# sEHnsor.net
KiCad netlist of a schematic drawn in EAGLE
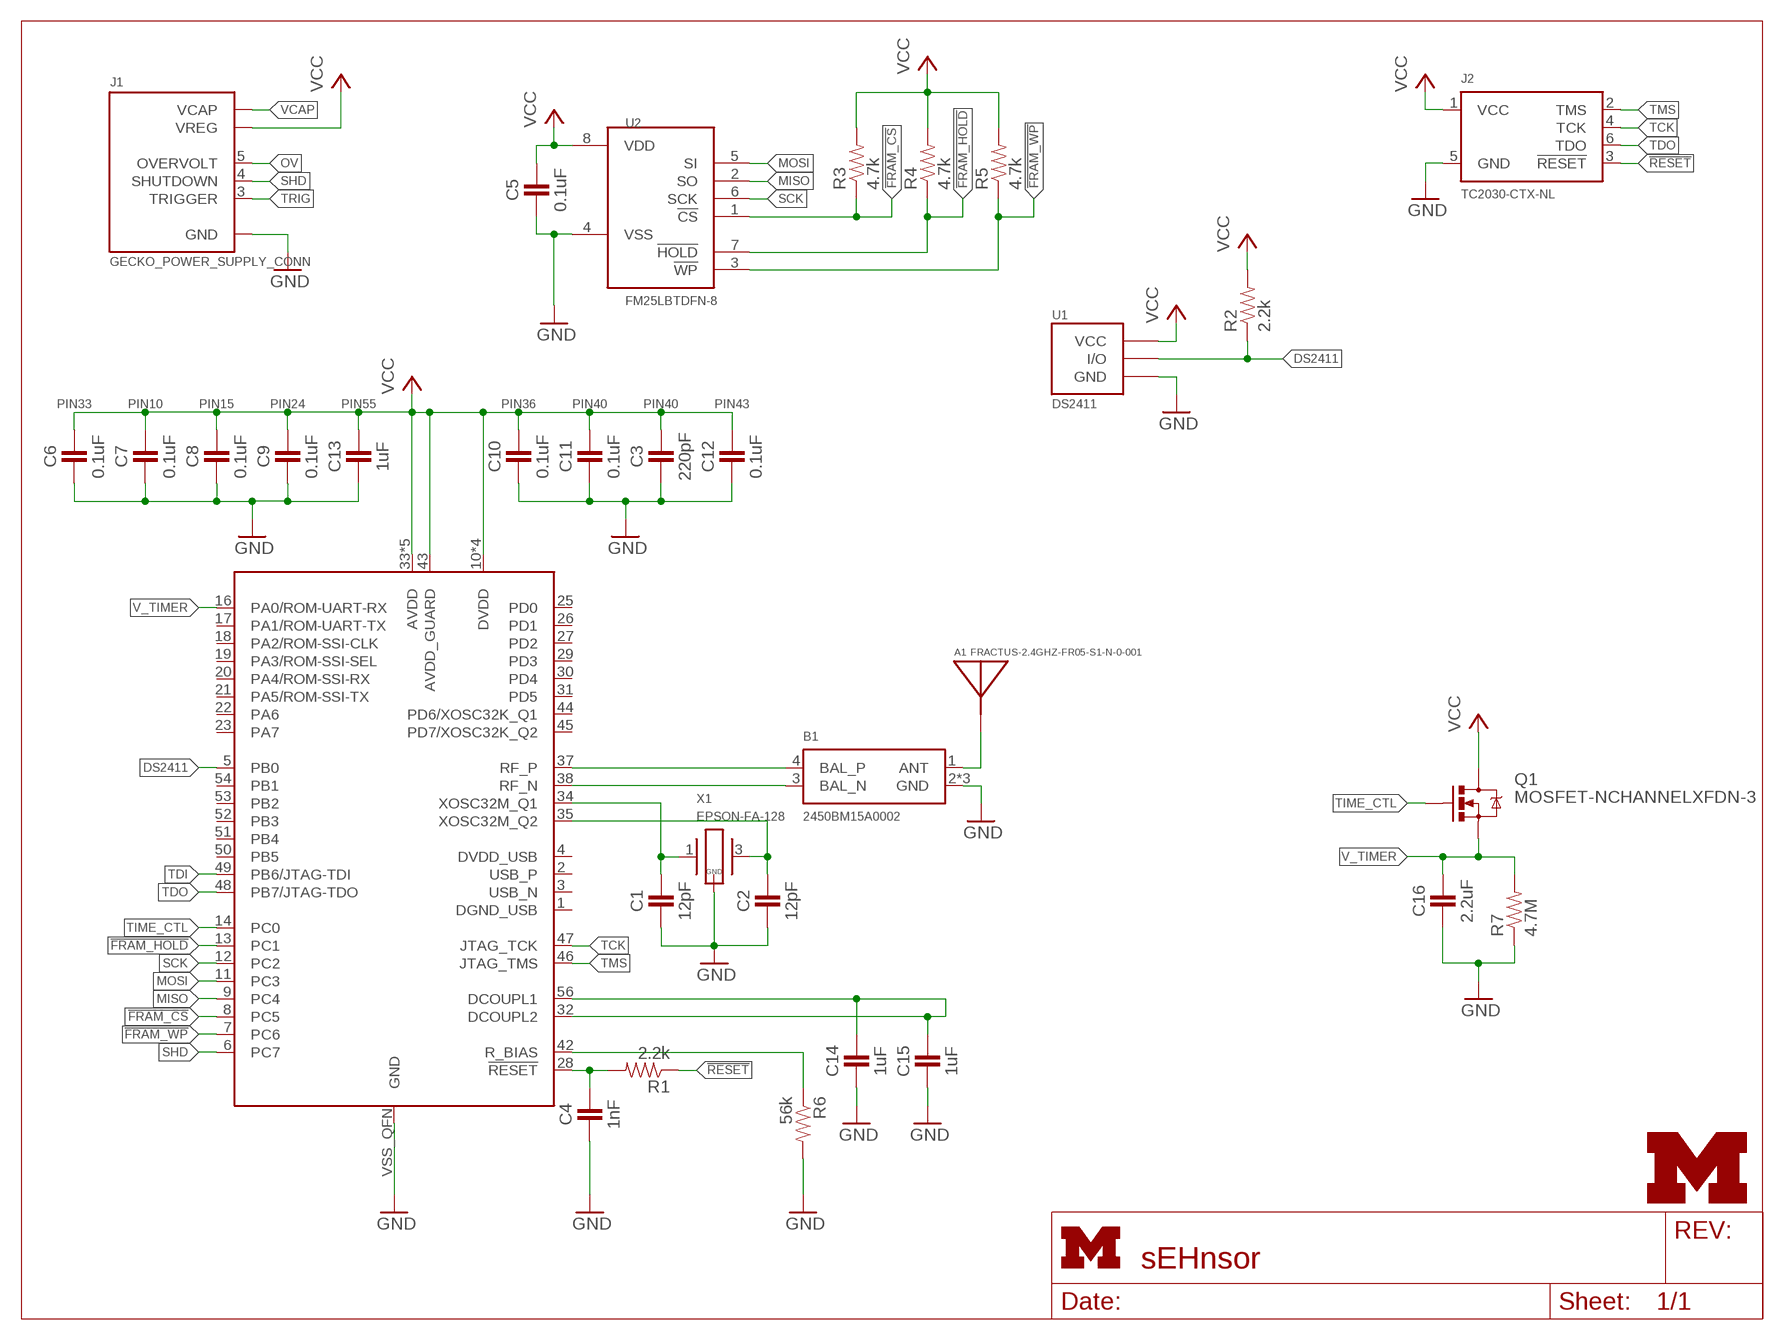
[diagram p0: schematic, sheet 1]

(export (version "E")
  (design (tool "Eeschema 10.0.6"))
  (components
    (comp (ref "A1")
      (value "FRACTUS-2.4GHZ-FR05-S1-N-0-001")
      (footprint "eagle-import:FRACTUS-ANTENNA-FR05-S1-N-0-001")
      (libsource (lib "eagle-import") (part "FRACTUS-2.4GHZ-FR05-S1-N-0-001"))
    )
    (comp (ref "B1")
      (value "2450BM15A0002")
      (footprint "eagle-import:2450BM")
      (libsource (lib "eagle-import") (part "2450BM15A0002"))
    )
    (comp (ref "C1")
      (value "12pF")
      (footprint "eagle-import:0402_CAP")
      (libsource (lib "eagle-import") (part "CAPACITOR"))
    )
    (comp (ref "C2")
      (value "12pF")
      (footprint "eagle-import:0402_CAP")
      (libsource (lib "eagle-import") (part "CAPACITOR"))
    )
    (comp (ref "C3")
      (value "220pF")
      (footprint "eagle-import:0402_CAP")
      (libsource (lib "eagle-import") (part "CAPACITOR"))
    )
    (comp (ref "C4")
      (value "1nF")
      (footprint "eagle-import:0402_CAP")
      (libsource (lib "eagle-import") (part "CAPACITOR"))
    )
    (comp (ref "C5")
      (value "0.1uF")
      (footprint "eagle-import:0402_CAP")
      (libsource (lib "eagle-import") (part "CAPACITOR"))
    )
    (comp (ref "C6")
      (value "0.1uF")
      (footprint "eagle-import:0402_CAP")
      (libsource (lib "eagle-import") (part "CAPACITOR"))
    )
    (comp (ref "C7")
      (value "0.1uF")
      (footprint "eagle-import:0402_CAP")
      (libsource (lib "eagle-import") (part "CAPACITOR"))
    )
    (comp (ref "C8")
      (value "0.1uF")
      (footprint "eagle-import:0402_CAP")
      (libsource (lib "eagle-import") (part "CAPACITOR"))
    )
    (comp (ref "C9")
      (value "0.1uF")
      (footprint "eagle-import:0402_CAP")
      (libsource (lib "eagle-import") (part "CAPACITOR"))
    )
    (comp (ref "C10")
      (value "0.1uF")
      (footprint "eagle-import:0402_CAP")
      (libsource (lib "eagle-import") (part "CAPACITOR"))
    )
    (comp (ref "C11")
      (value "0.1uF")
      (footprint "eagle-import:0402_CAP")
      (libsource (lib "eagle-import") (part "CAPACITOR"))
    )
    (comp (ref "C12")
      (value "0.1uF")
      (footprint "eagle-import:0402_CAP")
      (libsource (lib "eagle-import") (part "CAPACITOR"))
    )
    (comp (ref "C13")
      (value "1uF")
      (footprint "eagle-import:0402_CAP")
      (libsource (lib "eagle-import") (part "CAPACITOR"))
    )
    (comp (ref "C14")
      (value "1uF")
      (footprint "eagle-import:0402_CAP")
      (libsource (lib "eagle-import") (part "CAPACITOR"))
    )
    (comp (ref "C15")
      (value "1uF")
      (footprint "eagle-import:0402_CAP")
      (libsource (lib "eagle-import") (part "CAPACITOR"))
    )
    (comp (ref "C16")
      (value "2.2uF")
      (footprint "eagle-import:0402_CAP")
      (libsource (lib "eagle-import") (part "CAPACITOR"))
    )
    (comp (ref "J1")
      (value "GECKO_POWER_SUPPLY_CONN")
      (footprint "eagle-import:HEADER1X6_0.05IN")
      (libsource (lib "eagle-import") (part "GECKO_POWER_SUPPLY_CONN"))
    )
    (comp (ref "J2")
      (value "TC2030-CTX-NL")
      (footprint "eagle-import:TC2030-IDC-NL")
      (libsource (lib "eagle-import") (part "TC2030-CTX-NL"))
    )
    (comp (ref "Q1")
      (value "MOSFET-NCHANNELXFDN-3")
      (footprint "eagle-import:XFDFN-3")
      (libsource (lib "eagle-import") (part "MOSFET-NCHANNELXFDN-3"))
    )
    (comp (ref "R1")
      (value "2.2k")
      (footprint "eagle-import:0402_RES")
      (libsource (lib "eagle-import") (part "RESISTOR"))
    )
    (comp (ref "R2")
      (value "2.2k")
      (footprint "eagle-import:0402_RES")
      (libsource (lib "eagle-import") (part "RESISTOR"))
    )
    (comp (ref "R3")
      (value "4.7k")
      (footprint "eagle-import:0402_RES")
      (libsource (lib "eagle-import") (part "RESISTOR"))
    )
    (comp (ref "R4")
      (value "4.7k")
      (footprint "eagle-import:0402_RES")
      (libsource (lib "eagle-import") (part "RESISTOR"))
    )
    (comp (ref "R5")
      (value "4.7k")
      (footprint "eagle-import:0402_RES")
      (libsource (lib "eagle-import") (part "RESISTOR"))
    )
    (comp (ref "R6")
      (value "56k")
      (footprint "eagle-import:0402_RES")
      (libsource (lib "eagle-import") (part "RESISTOR"))
    )
    (comp (ref "R7")
      (value "4.7M")
      (footprint "eagle-import:0402_RES")
      (libsource (lib "eagle-import") (part "RESISTOR"))
    )
    (comp (ref "U$1")
      (value "UMICH_SOLID_SMALL")
      (footprint "eagle-import:UMICH_SOLID_75MIL")
      (libsource (lib "eagle-import") (part "UMICH_SOLID_SMALL"))
    )
    (comp (ref "U1")
      (value "DS2411")
      (footprint "eagle-import:SOT-23")
      (libsource (lib "eagle-import") (part "DS2411"))
    )
    (comp (ref "U2")
      (value "FM25LBTDFN-8")
      (footprint "eagle-import:TDFN-8")
      (libsource (lib "eagle-import") (part "FM25LBTDFN-8"))
    )
    (comp (ref "U3")
      (value "CC2538")
      (footprint "eagle-import:S-PVQFN-N56")
      (libsource (lib "eagle-import") (part "CC2538"))
    )
    (comp (ref "X1")
      (value "EPSON-FA-128")
      (footprint "eagle-import:FA-128")
      (libsource (lib "eagle-import") (part "EPSON-FA-128"))
    )
  )
  (nets
    (net (code "1") (name "/~{FRAM_CS}") (class "Default")
      (node (ref "R3") (pin "1") (pinfunction "1_1") (pintype "passive"))
      (node (ref "U2") (pin "1") (pinfunction "~{CS}_1") (pintype "bidirectional"))
      (node (ref "U3") (pin "8") (pinfunction "PC5_8") (pintype "bidirectional"))
    )
    (net (code "2") (name "/~{FRAM_HOLD}") (class "Default")
      (node (ref "R4") (pin "1") (pinfunction "1_1") (pintype "passive"))
      (node (ref "U2") (pin "7") (pinfunction "~{HOLD}_7") (pintype "bidirectional"))
      (node (ref "U3") (pin "13") (pinfunction "PC1_13") (pintype "bidirectional"))
    )
    (net (code "3") (name "/~{FRAM_WP}") (class "Default")
      (node (ref "R5") (pin "1") (pinfunction "1_1") (pintype "passive"))
      (node (ref "U2") (pin "3") (pinfunction "~{WP}_3") (pintype "bidirectional"))
      (node (ref "U3") (pin "7") (pinfunction "PC6_7") (pintype "bidirectional"))
    )
    (net (code "4") (name "/~{RESET}") (class "Default")
      (node (ref "J2") (pin "3") (pinfunction "~{RESET}_3") (pintype "bidirectional"))
      (node (ref "R1") (pin "1") (pinfunction "1_1") (pintype "passive"))
    )
    (net (code "5") (name "DS2411") (class "Default")
      (node (ref "R2") (pin "1") (pinfunction "1_1") (pintype "passive"))
      (node (ref "U1") (pin "1") (pinfunction "I/O_1") (pintype "bidirectional"))
      (node (ref "U3") (pin "5") (pinfunction "PB0_5") (pintype "bidirectional"))
    )
    (net (code "6") (name "GND") (class "Default")
      (node (ref "B1") (pin "2") (pinfunction "GND_2") (pintype "bidirectional"))
      (node (ref "B1") (pin "5") (pinfunction "GND_5") (pintype "bidirectional"))
      (node (ref "B1") (pin "6") (pinfunction "GND_6") (pintype "bidirectional"))
      (node (ref "C1") (pin "2") (pinfunction "2_2") (pintype "bidirectional"))
      (node (ref "C10") (pin "2") (pinfunction "2_2") (pintype "bidirectional"))
      (node (ref "C11") (pin "2") (pinfunction "2_2") (pintype "bidirectional"))
      (node (ref "C12") (pin "2") (pinfunction "2_2") (pintype "bidirectional"))
      (node (ref "C13") (pin "2") (pinfunction "2_2") (pintype "bidirectional"))
      (node (ref "C14") (pin "2") (pinfunction "2_2") (pintype "bidirectional"))
      (node (ref "C15") (pin "2") (pinfunction "2_2") (pintype "bidirectional"))
      (node (ref "C16") (pin "2") (pinfunction "2_2") (pintype "bidirectional"))
      (node (ref "C2") (pin "2") (pinfunction "2_2") (pintype "bidirectional"))
      (node (ref "C3") (pin "2") (pinfunction "2_2") (pintype "bidirectional"))
      (node (ref "C4") (pin "2") (pinfunction "2_2") (pintype "bidirectional"))
      (node (ref "C5") (pin "2") (pinfunction "2_2") (pintype "bidirectional"))
      (node (ref "C6") (pin "2") (pinfunction "2_2") (pintype "bidirectional"))
      (node (ref "C7") (pin "2") (pinfunction "2_2") (pintype "bidirectional"))
      (node (ref "C8") (pin "2") (pinfunction "2_2") (pintype "bidirectional"))
      (node (ref "C9") (pin "2") (pinfunction "2_2") (pintype "bidirectional"))
      (node (ref "J1") (pin "1") (pinfunction "GND_1") (pintype "bidirectional"))
      (node (ref "J2") (pin "5") (pinfunction "GND_5") (pintype "bidirectional"))
      (node (ref "R6") (pin "2") (pinfunction "2_2") (pintype "passive"))
      (node (ref "R7") (pin "1") (pinfunction "1_1") (pintype "passive"))
      (node (ref "U1") (pin "3") (pinfunction "GND_3") (pintype "bidirectional"))
      (node (ref "U2") (pin "4") (pinfunction "VSS_4") (pintype "bidirectional"))
      (node (ref "U3") (pin "VSS_QFN") (pinfunction "GND_VSS_QFN") (pintype "bidirectional"))
      (node (ref "X1") (pin "2") (pinfunction "GND_2") (pintype "bidirectional"))
      (node (ref "X1") (pin "4") (pinfunction "GND_4") (pintype "bidirectional"))
    )
    (net (code "7") (name "MISO") (class "Default")
      (node (ref "U2") (pin "2") (pinfunction "SO_2") (pintype "bidirectional"))
      (node (ref "U3") (pin "9") (pinfunction "PC4_9") (pintype "bidirectional"))
    )
    (net (code "8") (name "MOSI") (class "Default")
      (node (ref "U2") (pin "5") (pinfunction "SI_5") (pintype "bidirectional"))
      (node (ref "U3") (pin "11") (pinfunction "PC3_11") (pintype "bidirectional"))
    )
    (net (code "9") (name "Net-(A1-ANTENNA)") (class "Default")
      (node (ref "A1") (pin "1") (pinfunction "ANTENNA_1") (pintype "bidirectional"))
      (node (ref "B1") (pin "1") (pinfunction "ANT_1") (pintype "bidirectional"))
    )
    (net (code "10") (name "Net-(B1-BAL_N)") (class "Default")
      (node (ref "B1") (pin "3") (pinfunction "BAL_N_3") (pintype "bidirectional"))
      (node (ref "U3") (pin "38") (pinfunction "RF_N_38") (pintype "bidirectional"))
    )
    (net (code "11") (name "Net-(B1-BAL_P)") (class "Default")
      (node (ref "B1") (pin "4") (pinfunction "BAL_P_4") (pintype "bidirectional"))
      (node (ref "U3") (pin "37") (pinfunction "RF_P_37") (pintype "bidirectional"))
    )
    (net (code "12") (name "Net-(U3-DCOUPL1)") (class "Default")
      (node (ref "C14") (pin "1") (pinfunction "1_1") (pintype "bidirectional"))
      (node (ref "C15") (pin "1") (pinfunction "1_1") (pintype "bidirectional"))
      (node (ref "U3") (pin "32") (pinfunction "DCOUPL2_32") (pintype "bidirectional"))
      (node (ref "U3") (pin "56") (pinfunction "DCOUPL1_56") (pintype "bidirectional"))
    )
    (net (code "13") (name "Net-(U3-R_BIAS)") (class "Default")
      (node (ref "R6") (pin "1") (pinfunction "1_1") (pintype "passive"))
      (node (ref "U3") (pin "42") (pinfunction "R_BIAS_42") (pintype "bidirectional"))
    )
    (net (code "14") (name "Net-(U3-XOSC32M_Q1)") (class "Default")
      (node (ref "C1") (pin "1") (pinfunction "1_1") (pintype "bidirectional"))
      (node (ref "U3") (pin "34") (pinfunction "XOSC32M_Q1_34") (pintype "bidirectional"))
      (node (ref "X1") (pin "1") (pinfunction "1_1") (pintype "bidirectional"))
    )
    (net (code "15") (name "Net-(U3-XOSC32M_Q2)") (class "Default")
      (node (ref "C2") (pin "1") (pinfunction "1_1") (pintype "bidirectional"))
      (node (ref "U3") (pin "35") (pinfunction "XOSC32M_Q2_35") (pintype "bidirectional"))
      (node (ref "X1") (pin "3") (pinfunction "2_3") (pintype "bidirectional"))
    )
    (net (code "16") (name "Net-(U3-~{RESET})") (class "Default")
      (node (ref "C4") (pin "1") (pinfunction "1_1") (pintype "bidirectional"))
      (node (ref "R1") (pin "2") (pinfunction "2_2") (pintype "passive"))
      (node (ref "U3") (pin "28") (pinfunction "~{RESET}_28") (pintype "bidirectional"))
    )
    (net (code "17") (name "OV") (class "Default")
      (node (ref "J1") (pin "5") (pinfunction "OVERVOLT_5") (pintype "bidirectional"))
    )
    (net (code "18") (name "SCK") (class "Default")
      (node (ref "U2") (pin "6") (pinfunction "SCK_6") (pintype "bidirectional"))
      (node (ref "U3") (pin "12") (pinfunction "PC2_12") (pintype "bidirectional"))
    )
    (net (code "19") (name "SHD") (class "Default")
      (node (ref "J1") (pin "4") (pinfunction "SHUTDOWN_4") (pintype "bidirectional"))
      (node (ref "U3") (pin "6") (pinfunction "PC7_6") (pintype "bidirectional"))
    )
    (net (code "20") (name "TCK") (class "Default")
      (node (ref "J2") (pin "4") (pinfunction "TCK_4") (pintype "bidirectional"))
      (node (ref "U3") (pin "47") (pinfunction "JTAG_TCK_47") (pintype "bidirectional"))
    )
    (net (code "21") (name "TDI") (class "Default")
      (node (ref "U3") (pin "49") (pinfunction "PB6/JTAG-TDI_49") (pintype "bidirectional"))
    )
    (net (code "22") (name "TDO") (class "Default")
      (node (ref "J2") (pin "6") (pinfunction "TDO_6") (pintype "bidirectional"))
      (node (ref "U3") (pin "48") (pinfunction "PB7/JTAG-TDO_48") (pintype "bidirectional"))
    )
    (net (code "23") (name "TIME_CTL") (class "Default")
      (node (ref "Q1") (pin "G") (pinfunction "G_G") (pintype "passive"))
      (node (ref "U3") (pin "14") (pinfunction "PC0_14") (pintype "bidirectional"))
    )
    (net (code "24") (name "TMS") (class "Default")
      (node (ref "J2") (pin "2") (pinfunction "TMS_2") (pintype "bidirectional"))
      (node (ref "U3") (pin "46") (pinfunction "JTAG_TMS_46") (pintype "bidirectional"))
    )
    (net (code "25") (name "TRIG") (class "Default")
      (node (ref "J1") (pin "3") (pinfunction "TRIGGER_3") (pintype "bidirectional"))
    )
    (net (code "26") (name "VCAP") (class "Default")
      (node (ref "J1") (pin "6") (pinfunction "VCAP_6") (pintype "output"))
    )
    (net (code "27") (name "VCC") (class "Default")
      (node (ref "C10") (pin "1") (pinfunction "1_1") (pintype "bidirectional"))
      (node (ref "C11") (pin "1") (pinfunction "1_1") (pintype "bidirectional"))
      (node (ref "C12") (pin "1") (pinfunction "1_1") (pintype "bidirectional"))
      (node (ref "C13") (pin "1") (pinfunction "1_1") (pintype "bidirectional"))
      (node (ref "C3") (pin "1") (pinfunction "1_1") (pintype "bidirectional"))
      (node (ref "C5") (pin "1") (pinfunction "1_1") (pintype "bidirectional"))
      (node (ref "C6") (pin "1") (pinfunction "1_1") (pintype "bidirectional"))
      (node (ref "C7") (pin "1") (pinfunction "1_1") (pintype "bidirectional"))
      (node (ref "C8") (pin "1") (pinfunction "1_1") (pintype "bidirectional"))
      (node (ref "C9") (pin "1") (pinfunction "1_1") (pintype "bidirectional"))
      (node (ref "J1") (pin "2") (pinfunction "VREG_2") (pintype "bidirectional"))
      (node (ref "J2") (pin "1") (pinfunction "VCC_1") (pintype "bidirectional"))
      (node (ref "Q1") (pin "D") (pinfunction "D_D") (pintype "passive"))
      (node (ref "R2") (pin "2") (pinfunction "2_2") (pintype "passive"))
      (node (ref "R3") (pin "2") (pinfunction "2_2") (pintype "passive"))
      (node (ref "R4") (pin "2") (pinfunction "2_2") (pintype "passive"))
      (node (ref "R5") (pin "2") (pinfunction "2_2") (pintype "passive"))
      (node (ref "U1") (pin "2") (pinfunction "VCC_2") (pintype "bidirectional"))
      (node (ref "U2") (pin "8") (pinfunction "VDD_8") (pintype "bidirectional"))
      (node (ref "U3") (pin "10") (pinfunction "DVDD_10") (pintype "bidirectional"))
      (node (ref "U3") (pin "15") (pinfunction "DVDD_15") (pintype "bidirectional"))
      (node (ref "U3") (pin "24") (pinfunction "DVDD_24") (pintype "bidirectional"))
      (node (ref "U3") (pin "33") (pinfunction "AVDD_33") (pintype "bidirectional"))
      (node (ref "U3") (pin "36") (pinfunction "AVDD_36") (pintype "bidirectional"))
      (node (ref "U3") (pin "39") (pinfunction "AVDD_39") (pintype "bidirectional"))
      (node (ref "U3") (pin "40") (pinfunction "AVDD_40") (pintype "bidirectional"))
      (node (ref "U3") (pin "41") (pinfunction "AVDD_41") (pintype "bidirectional"))
      (node (ref "U3") (pin "43") (pinfunction "AVDD_GUARD_43") (pintype "bidirectional"))
      (node (ref "U3") (pin "55") (pinfunction "DVDD_55") (pintype "bidirectional"))
    )
    (net (code "28") (name "V_TIMER") (class "Default")
      (node (ref "C16") (pin "1") (pinfunction "1_1") (pintype "bidirectional"))
      (node (ref "Q1") (pin "S") (pinfunction "S_S") (pintype "passive"))
      (node (ref "R7") (pin "2") (pinfunction "2_2") (pintype "passive"))
      (node (ref "U3") (pin "16") (pinfunction "PA0/ROM-UART-RX_16") (pintype "bidirectional"))
    )
    (net (code "29") (name "unconnected-(U3-DGND_USB-Pad1)") (class "Default")
      (node (ref "U3") (pin "1") (pinfunction "DGND_USB_1") (pintype "bidirectional"))
    )
    (net (code "30") (name "unconnected-(U3-DVDD_USB-Pad4)") (class "Default")
      (node (ref "U3") (pin "4") (pinfunction "DVDD_USB_4") (pintype "bidirectional"))
    )
    (net (code "31") (name "unconnected-(U3-PA1{slash}ROM-UART-TX-Pad17)") (class "Default")
      (node (ref "U3") (pin "17") (pinfunction "PA1/ROM-UART-TX_17") (pintype "bidirectional"))
    )
    (net (code "32") (name "unconnected-(U3-PA2{slash}ROM-SSI-CLK-Pad18)") (class "Default")
      (node (ref "U3") (pin "18") (pinfunction "PA2/ROM-SSI-CLK_18") (pintype "bidirectional"))
    )
    (net (code "33") (name "unconnected-(U3-PA3{slash}ROM-SSI-SEL-Pad19)") (class "Default")
      (node (ref "U3") (pin "19") (pinfunction "PA3/ROM-SSI-SEL_19") (pintype "bidirectional"))
    )
    (net (code "34") (name "unconnected-(U3-PA4{slash}ROM-SSI-RX-Pad20)") (class "Default")
      (node (ref "U3") (pin "20") (pinfunction "PA4/ROM-SSI-RX_20") (pintype "bidirectional"))
    )
    (net (code "35") (name "unconnected-(U3-PA5{slash}ROM-SSI-TX-Pad21)") (class "Default")
      (node (ref "U3") (pin "21") (pinfunction "PA5/ROM-SSI-TX_21") (pintype "bidirectional"))
    )
    (net (code "36") (name "unconnected-(U3-PA6-Pad22)") (class "Default")
      (node (ref "U3") (pin "22") (pinfunction "PA6_22") (pintype "bidirectional"))
    )
    (net (code "37") (name "unconnected-(U3-PA7-Pad23)") (class "Default")
      (node (ref "U3") (pin "23") (pinfunction "PA7_23") (pintype "bidirectional"))
    )
    (net (code "38") (name "unconnected-(U3-PB1-Pad54)") (class "Default")
      (node (ref "U3") (pin "54") (pinfunction "PB1_54") (pintype "bidirectional"))
    )
    (net (code "39") (name "unconnected-(U3-PB2-Pad53)") (class "Default")
      (node (ref "U3") (pin "53") (pinfunction "PB2_53") (pintype "bidirectional"))
    )
    (net (code "40") (name "unconnected-(U3-PB3-Pad52)") (class "Default")
      (node (ref "U3") (pin "52") (pinfunction "PB3_52") (pintype "bidirectional"))
    )
    (net (code "41") (name "unconnected-(U3-PB4-Pad51)") (class "Default")
      (node (ref "U3") (pin "51") (pinfunction "PB4_51") (pintype "bidirectional"))
    )
    (net (code "42") (name "unconnected-(U3-PB5-Pad50)") (class "Default")
      (node (ref "U3") (pin "50") (pinfunction "PB5_50") (pintype "bidirectional"))
    )
    (net (code "43") (name "unconnected-(U3-PD0-Pad25)") (class "Default")
      (node (ref "U3") (pin "25") (pinfunction "PD0_25") (pintype "bidirectional"))
    )
    (net (code "44") (name "unconnected-(U3-PD1-Pad26)") (class "Default")
      (node (ref "U3") (pin "26") (pinfunction "PD1_26") (pintype "bidirectional"))
    )
    (net (code "45") (name "unconnected-(U3-PD2-Pad27)") (class "Default")
      (node (ref "U3") (pin "27") (pinfunction "PD2_27") (pintype "bidirectional"))
    )
    (net (code "46") (name "unconnected-(U3-PD3-Pad29)") (class "Default")
      (node (ref "U3") (pin "29") (pinfunction "PD3_29") (pintype "bidirectional"))
    )
    (net (code "47") (name "unconnected-(U3-PD4-Pad30)") (class "Default")
      (node (ref "U3") (pin "30") (pinfunction "PD4_30") (pintype "bidirectional"))
    )
    (net (code "48") (name "unconnected-(U3-PD5-Pad31)") (class "Default")
      (node (ref "U3") (pin "31") (pinfunction "PD5_31") (pintype "bidirectional"))
    )
    (net (code "49") (name "unconnected-(U3-PD6{slash}XOSC32K_Q1-Pad44)") (class "Default")
      (node (ref "U3") (pin "44") (pinfunction "PD6/XOSC32K_Q1_44") (pintype "bidirectional"))
    )
    (net (code "50") (name "unconnected-(U3-PD7{slash}XOSC32K_Q2-Pad45)") (class "Default")
      (node (ref "U3") (pin "45") (pinfunction "PD7/XOSC32K_Q2_45") (pintype "bidirectional"))
    )
    (net (code "51") (name "unconnected-(U3-USB_N-Pad3)") (class "Default")
      (node (ref "U3") (pin "3") (pinfunction "USB_N_3") (pintype "bidirectional"))
    )
    (net (code "52") (name "unconnected-(U3-USB_P-Pad2)") (class "Default")
      (node (ref "U3") (pin "2") (pinfunction "USB_P_2") (pintype "bidirectional"))
    )
  )
)
